# ComClone2.net
KiCad netlist of a schematic drawn in EAGLE
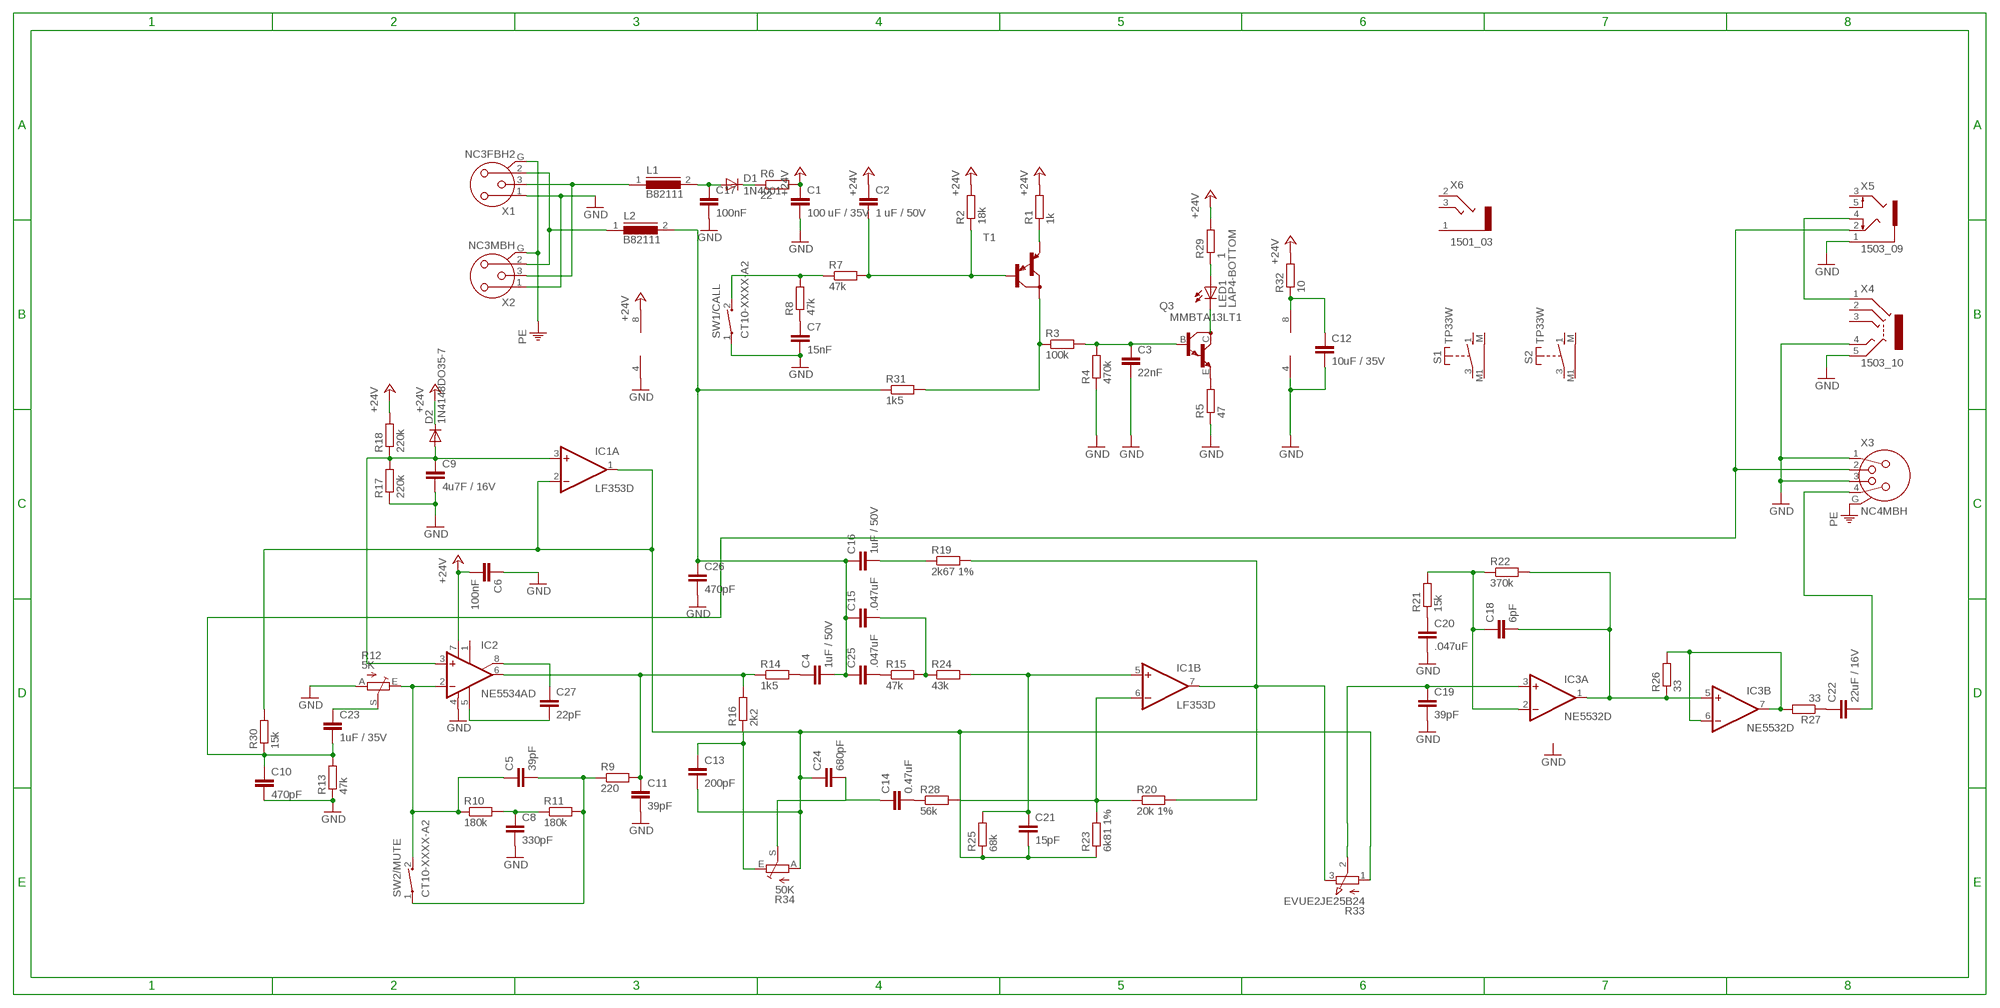
[diagram p0: schematic, sheet 1]

(export (version "E")
  (design (tool "Eeschema 10.0.6"))
  (components
    (comp (ref "C1")
      (value "100 uF / 35V")
      (footprint "eagle-import:C1206")
      (libsource (lib "eagle-import") (part "C-EUC1206"))
    )
    (comp (ref "C2")
      (value "1 uF / 50V")
      (footprint "eagle-import:C1206")
      (libsource (lib "eagle-import") (part "C-EUC1206"))
    )
    (comp (ref "C3")
      (value "22nF")
      (footprint "eagle-import:C0603")
      (libsource (lib "eagle-import") (part "C-EUC0603"))
    )
    (comp (ref "C4")
      (value "1uF / 50V")
      (footprint "eagle-import:C1206")
      (libsource (lib "eagle-import") (part "C-EUC1206"))
    )
    (comp (ref "C5")
      (value "39pF")
      (footprint "eagle-import:C0603")
      (libsource (lib "eagle-import") (part "C-EUC0603"))
    )
    (comp (ref "C6")
      (value "100nF")
      (footprint "eagle-import:C1206")
      (libsource (lib "eagle-import") (part "C-EUC1206"))
    )
    (comp (ref "C7")
      (value "15nF")
      (footprint "eagle-import:C0603")
      (libsource (lib "eagle-import") (part "C-EUC0603"))
    )
    (comp (ref "C8")
      (value "330pF")
      (footprint "eagle-import:C0603")
      (libsource (lib "eagle-import") (part "C-EUC0603"))
    )
    (comp (ref "C9")
      (value "4u7F / 16V")
      (footprint "eagle-import:C1206")
      (libsource (lib "eagle-import") (part "C-EUC1206"))
    )
    (comp (ref "C10")
      (value "470pF")
      (footprint "eagle-import:C0603")
      (libsource (lib "eagle-import") (part "C-EUC0603"))
    )
    (comp (ref "C11")
      (value "39pF")
      (footprint "eagle-import:C0603")
      (libsource (lib "eagle-import") (part "C-EUC0603"))
    )
    (comp (ref "C12")
      (value "10uF / 35V")
      (footprint "eagle-import:C1206")
      (libsource (lib "eagle-import") (part "C-EUC1206"))
    )
    (comp (ref "C13")
      (value "200pF")
      (footprint "eagle-import:C0603")
      (libsource (lib "eagle-import") (part "C-EUC0603"))
    )
    (comp (ref "C14")
      (value "0.47uF")
      (footprint "eagle-import:C0603")
      (libsource (lib "eagle-import") (part "C-EUC0603"))
    )
    (comp (ref "C15")
      (value ".047uF")
      (footprint "eagle-import:C1206")
      (libsource (lib "eagle-import") (part "C-EUC1206"))
    )
    (comp (ref "C16")
      (value "1uF / 50V")
      (footprint "eagle-import:C3225")
      (libsource (lib "eagle-import") (part "C-EUC3225"))
    )
    (comp (ref "C17")
      (value "100nF")
      (footprint "eagle-import:C1206")
      (libsource (lib "eagle-import") (part "C-EUC1206"))
    )
    (comp (ref "C18")
      (value "6pF")
      (footprint "eagle-import:C1206")
      (libsource (lib "eagle-import") (part "C-EUC1206"))
    )
    (comp (ref "C19")
      (value "39pF")
      (footprint "eagle-import:C1206")
      (libsource (lib "eagle-import") (part "C-EUC1206"))
    )
    (comp (ref "C20")
      (value ".047uF")
      (footprint "eagle-import:C1206")
      (libsource (lib "eagle-import") (part "C-EUC1206"))
    )
    (comp (ref "C21")
      (value "15pF")
      (footprint "eagle-import:C1206")
      (libsource (lib "eagle-import") (part "C-EUC1206"))
    )
    (comp (ref "C22")
      (value "22uF / 16V")
      (footprint "eagle-import:C1206")
      (libsource (lib "eagle-import") (part "C-EUC1206"))
    )
    (comp (ref "C23")
      (value "1uF / 35V")
      (footprint "eagle-import:C1206")
      (libsource (lib "eagle-import") (part "C-EUC1206"))
    )
    (comp (ref "C24")
      (value "680pF")
      (footprint "eagle-import:C0603")
      (libsource (lib "eagle-import") (part "C-EUC0603"))
    )
    (comp (ref "C25")
      (value ".047uF")
      (footprint "eagle-import:C0603")
      (libsource (lib "eagle-import") (part "C-EUC0603"))
    )
    (comp (ref "C26")
      (value "470pF")
      (footprint "eagle-import:C0603")
      (libsource (lib "eagle-import") (part "C-EUC0603"))
    )
    (comp (ref "C27")
      (value "22pF")
      (footprint "eagle-import:C0603")
      (libsource (lib "eagle-import") (part "C-EUC0603"))
    )
    (comp (ref "D1")
      (value "1N4001")
      (footprint "eagle-import:DO41-10")
      (libsource (lib "eagle-import") (part "1N4004"))
    )
    (comp (ref "D2")
      (value "1N4148DO35-7")
      (footprint "eagle-import:DO35-7")
      (libsource (lib "eagle-import") (part "1N4148DO35-7"))
    )
    (comp (ref "IC1")
      (value "LF353D")
      (footprint "eagle-import:SO08")
      (libsource (lib "eagle-import") (part "LF353D"))
    )
    (comp (ref "IC2")
      (value "NE5534AD")
      (footprint "eagle-import:SO08")
      (libsource (lib "eagle-import") (part "NE5534DA"))
    )
    (comp (ref "IC3")
      (value "NE5532D")
      (footprint "eagle-import:SO08")
      (libsource (lib "eagle-import") (part "NE5532D"))
    )
    (comp (ref "L1")
      (value "B82111")
      (footprint "eagle-import:SUKW1-30")
      (libsource (lib "eagle-import") (part "B82111"))
    )
    (comp (ref "L2")
      (value "B82111")
      (footprint "eagle-import:SUKW1-30")
      (libsource (lib "eagle-import") (part "B82111"))
    )
    (comp (ref "LED1")
      (value "LAP4-BOTTOM")
      (footprint "eagle-import:P47F-BOTTOM")
      (libsource (lib "eagle-import") (part "P4-BOTTOMLA"))
    )
    (comp (ref "Q3")
      (value "MMBTA13LT1")
      (footprint "eagle-import:SOT23-BEC")
      (libsource (lib "eagle-import") (part "MMBTA13LT1"))
    )
    (comp (ref "R1")
      (value "1k")
      (footprint "eagle-import:R0603")
      (libsource (lib "eagle-import") (part "R-EU_R0603"))
    )
    (comp (ref "R2")
      (value "18k")
      (footprint "eagle-import:R0603")
      (libsource (lib "eagle-import") (part "R-EU_R0603"))
    )
    (comp (ref "R3")
      (value "100k")
      (footprint "eagle-import:R0603")
      (libsource (lib "eagle-import") (part "R-EU_R0603"))
    )
    (comp (ref "R4")
      (value "470k")
      (footprint "eagle-import:R0603")
      (libsource (lib "eagle-import") (part "R-EU_R0603"))
    )
    (comp (ref "R5")
      (value "47")
      (footprint "eagle-import:M1206")
      (libsource (lib "eagle-import") (part "R-EU_M1206"))
    )
    (comp (ref "R6")
      (value "22")
      (footprint "eagle-import:M1206")
      (libsource (lib "eagle-import") (part "R-EU_M1206"))
    )
    (comp (ref "R7")
      (value "47k")
      (footprint "eagle-import:R0603")
      (libsource (lib "eagle-import") (part "R-EU_R0603"))
    )
    (comp (ref "R8")
      (value "47k")
      (footprint "eagle-import:R0603")
      (libsource (lib "eagle-import") (part "R-EU_R0603"))
    )
    (comp (ref "R9")
      (value "220")
      (footprint "eagle-import:R0603")
      (libsource (lib "eagle-import") (part "R-EU_R0603"))
    )
    (comp (ref "R10")
      (value "180k")
      (footprint "eagle-import:R0603")
      (libsource (lib "eagle-import") (part "R-EU_R0603"))
    )
    (comp (ref "R11")
      (value "180k")
      (footprint "eagle-import:R0603")
      (libsource (lib "eagle-import") (part "R-EU_R0603"))
    )
    (comp (ref "R12")
      (value "5K")
      (footprint "eagle-import:PT-10S")
      (libsource (lib "eagle-import") (part "TRIM_EU-PT10S"))
    )
    (comp (ref "R13")
      (value "47k")
      (footprint "eagle-import:R0603")
      (libsource (lib "eagle-import") (part "R-EU_R0603"))
    )
    (comp (ref "R14")
      (value "1k5")
      (footprint "eagle-import:R0603")
      (libsource (lib "eagle-import") (part "R-EU_R0603"))
    )
    (comp (ref "R15")
      (value "47k")
      (footprint "eagle-import:R0603")
      (libsource (lib "eagle-import") (part "R-EU_R0603"))
    )
    (comp (ref "R16")
      (value "2k2")
      (footprint "eagle-import:R0603")
      (libsource (lib "eagle-import") (part "R-EU_R0603"))
    )
    (comp (ref "R17")
      (value "220k")
      (footprint "eagle-import:M1206")
      (libsource (lib "eagle-import") (part "R-EU_M1206"))
    )
    (comp (ref "R18")
      (value "220k")
      (footprint "eagle-import:M1206")
      (libsource (lib "eagle-import") (part "R-EU_M1206"))
    )
    (comp (ref "R19")
      (value "2k67 1%")
      (footprint "eagle-import:M1206")
      (libsource (lib "eagle-import") (part "R-EU_M1206"))
    )
    (comp (ref "R20")
      (value "20k 1%")
      (footprint "eagle-import:R0603")
      (libsource (lib "eagle-import") (part "R-EU_R0603"))
    )
    (comp (ref "R21")
      (value "15k")
      (footprint "eagle-import:M1206")
      (libsource (lib "eagle-import") (part "R-EU_M1206"))
    )
    (comp (ref "R22")
      (value "370k")
      (footprint "eagle-import:R0603")
      (libsource (lib "eagle-import") (part "R-EU_R0603"))
    )
    (comp (ref "R23")
      (value "6k81 1%")
      (footprint "eagle-import:R0603")
      (libsource (lib "eagle-import") (part "R-EU_R0603"))
    )
    (comp (ref "R24")
      (value "43k")
      (footprint "eagle-import:R0603")
      (libsource (lib "eagle-import") (part "R-EU_R0603"))
    )
    (comp (ref "R25")
      (value "68k")
      (footprint "eagle-import:R0603")
      (libsource (lib "eagle-import") (part "R-EU_R0603"))
    )
    (comp (ref "R26")
      (value "33")
      (footprint "eagle-import:M1206")
      (libsource (lib "eagle-import") (part "R-EU_M1206"))
    )
    (comp (ref "R27")
      (value "33")
      (footprint "eagle-import:M1206")
      (libsource (lib "eagle-import") (part "R-EU_M1206"))
    )
    (comp (ref "R28")
      (value "56k")
      (footprint "eagle-import:R0603")
      (libsource (lib "eagle-import") (part "R-EU_R0603"))
    )
    (comp (ref "R29")
      (value "1")
      (footprint "eagle-import:M1206")
      (libsource (lib "eagle-import") (part "R-EU_M1206"))
    )
    (comp (ref "R30")
      (value "15k")
      (footprint "eagle-import:R0603")
      (libsource (lib "eagle-import") (part "R-EU_R0603"))
    )
    (comp (ref "R31")
      (value "1k5")
      (footprint "eagle-import:R0603")
      (libsource (lib "eagle-import") (part "R-EU_R0603"))
    )
    (comp (ref "R32")
      (value "10")
      (footprint "eagle-import:M1206")
      (libsource (lib "eagle-import") (part "R-EU_M1206"))
    )
    (comp (ref "R33")
      (value "EVUE2JE25B24")
      (footprint "eagle-import:EVUEXXJ")
      (libsource (lib "eagle-import") (part "EVUJE2"))
    )
    (comp (ref "R34")
      (value "50K")
      (footprint "eagle-import:PT-10S")
      (libsource (lib "eagle-import") (part "TRIM_EU-PT10S"))
    )
    (comp (ref "S1")
      (value "TP33W")
      (footprint "eagle-import:TP33W")
      (libsource (lib "eagle-import") (part "TP33W"))
    )
    (comp (ref "S2")
      (value "TP33W")
      (footprint "eagle-import:TP33W")
      (libsource (lib "eagle-import") (part "TP33W"))
    )
    (comp (ref "SW1/CALL")
      (value "CT10-XXXX-A2")
      (footprint "eagle-import:CT10-XXXX-A2")
      (libsource (lib "eagle-import") (part "CT10-XXXX-A2"))
    )
    (comp (ref "SW2/MUTE")
      (value "CT10-XXXX-A2")
      (footprint "eagle-import:CT10-XXXX-A2")
      (libsource (lib "eagle-import") (part "CT10-XXXX-A2"))
    )
    (comp (ref "T1")
      (value "MMBTA64LT1-PNP_DARL-SOT23-BEC")
      (footprint "eagle-import:SOT23-BEC")
      (libsource (lib "eagle-import") (part "-PNP_DARL-SOT23-BECMMBTA64LT1"))
    )
    (comp (ref "X1")
      (value "NC3FBH2")
      (footprint "eagle-import:NC3FBH2")
      (libsource (lib "eagle-import") (part "NC3FBH2"))
    )
    (comp (ref "X2")
      (value "NC3MBH")
      (footprint "eagle-import:NC3MBH")
      (fields (field (name "MF") "NEUTRIK"))
      (libsource (lib "eagle-import") (part "NC3MBH"))
    )
    (comp (ref "X3")
      (value "NC4MBH")
      (footprint "eagle-import:NC4MBH")
      (libsource (lib "eagle-import") (part "NC4MBH"))
    )
    (comp (ref "X4")
      (value "1503_10")
      (footprint "eagle-import:1503_10")
      (libsource (lib "eagle-import") (part "1503_10"))
    )
    (comp (ref "X5")
      (value "1503_09")
      (footprint "eagle-import:1503_09")
      (libsource (lib "eagle-import") (part "1503_09"))
    )
    (comp (ref "X6")
      (value "1501_03")
      (footprint "eagle-import:1501_03")
      (libsource (lib "eagle-import") (part "1501_03"))
    )
  )
  (nets
    (net (code "1") (name "+24V") (class "Default")
      (node (ref "C1") (pin "1") (pinfunction "1_1") (pintype "passive"))
      (node (ref "C2") (pin "1") (pinfunction "1_1") (pintype "passive"))
      (node (ref "C6") (pin "2") (pinfunction "2_2") (pintype "passive"))
      (node (ref "D2") (pin "C") (pinfunction "C_C") (pintype "passive"))
      (node (ref "IC1") (pin "8") (pinfunction "V+_8") (pintype "power_in"))
      (node (ref "IC2") (pin "7") (pinfunction "V+_7") (pintype "power_in"))
      (node (ref "R1") (pin "2") (pinfunction "2_2") (pintype "passive"))
      (node (ref "R18") (pin "2") (pinfunction "2_2") (pintype "passive"))
      (node (ref "R2") (pin "2") (pinfunction "2_2") (pintype "passive"))
      (node (ref "R29") (pin "2") (pinfunction "2_2") (pintype "passive"))
      (node (ref "R32") (pin "2") (pinfunction "2_2") (pintype "passive"))
      (node (ref "R6") (pin "2") (pinfunction "2_2") (pintype "passive"))
    )
    (net (code "2") (name "GND") (class "Default")
      (node (ref "C1") (pin "2") (pinfunction "2_2") (pintype "passive"))
      (node (ref "C10") (pin "2") (pinfunction "2_2") (pintype "passive"))
      (node (ref "C11") (pin "2") (pinfunction "2_2") (pintype "passive"))
      (node (ref "C12") (pin "2") (pinfunction "2_2") (pintype "passive"))
      (node (ref "C17") (pin "2") (pinfunction "2_2") (pintype "passive"))
      (node (ref "C19") (pin "2") (pinfunction "2_2") (pintype "passive"))
      (node (ref "C20") (pin "2") (pinfunction "2_2") (pintype "passive"))
      (node (ref "C26") (pin "2") (pinfunction "2_2") (pintype "passive"))
      (node (ref "C3") (pin "2") (pinfunction "2_2") (pintype "passive"))
      (node (ref "C6") (pin "1") (pinfunction "1_1") (pintype "passive"))
      (node (ref "C7") (pin "2") (pinfunction "2_2") (pintype "passive"))
      (node (ref "C8") (pin "2") (pinfunction "2_2") (pintype "passive"))
      (node (ref "C9") (pin "2") (pinfunction "2_2") (pintype "passive"))
      (node (ref "IC1") (pin "4") (pinfunction "V-_4") (pintype "power_in"))
      (node (ref "IC2") (pin "4") (pinfunction "V-_4") (pintype "power_in"))
      (node (ref "IC3") (pin "4") (pinfunction "V-_4") (pintype "power_in"))
      (node (ref "R12") (pin "A") (pinfunction "A_A") (pintype "passive"))
      (node (ref "R13") (pin "1") (pinfunction "1_1") (pintype "passive"))
      (node (ref "R17") (pin "1") (pinfunction "1_1") (pintype "passive"))
      (node (ref "R4") (pin "1") (pinfunction "1_1") (pintype "passive"))
      (node (ref "R5") (pin "1") (pinfunction "1_1") (pintype "passive"))
      (node (ref "SW1/CALL") (pin "1") (pinfunction "1_1") (pintype "passive"))
      (node (ref "X1") (pin "1") (pinfunction "1_1") (pintype "passive"))
      (node (ref "X2") (pin "1") (pinfunction "1_1") (pintype "passive"))
      (node (ref "X3") (pin "1") (pinfunction "1_1") (pintype "passive"))
      (node (ref "X3") (pin "3") (pinfunction "3_3") (pintype "passive"))
      (node (ref "X4") (pin "4") (pinfunction "4_4") (pintype "passive"))
      (node (ref "X4") (pin "5") (pinfunction "5_5") (pintype "passive"))
      (node (ref "X5") (pin "1") (pinfunction "1_1") (pintype "passive"))
    )
    (net (code "3") (name "Net-(C2-Pad2)") (class "Default")
      (node (ref "C2") (pin "2") (pinfunction "2_2") (pintype "passive"))
      (node (ref "R2") (pin "1") (pinfunction "1_1") (pintype "passive"))
      (node (ref "R7") (pin "2") (pinfunction "2_2") (pintype "passive"))
      (node (ref "T1") (pin "B") (pinfunction "B_B") (pintype "passive"))
    )
    (net (code "4") (name "Net-(C3-Pad1)") (class "Default")
      (node (ref "C3") (pin "1") (pinfunction "1_1") (pintype "passive"))
      (node (ref "Q3") (pin "B") (pinfunction "B_B") (pintype "passive"))
      (node (ref "R3") (pin "2") (pinfunction "2_2") (pintype "passive"))
      (node (ref "R4") (pin "2") (pinfunction "2_2") (pintype "passive"))
    )
    (net (code "5") (name "Net-(C4-Pad1)") (class "Default")
      (node (ref "C4") (pin "1") (pinfunction "1_1") (pintype "passive"))
      (node (ref "R14") (pin "2") (pinfunction "2_2") (pintype "passive"))
    )
    (net (code "6") (name "Net-(C5-Pad2)") (class "Default")
      (node (ref "C5") (pin "2") (pinfunction "2_2") (pintype "passive"))
      (node (ref "R11") (pin "2") (pinfunction "2_2") (pintype "passive"))
      (node (ref "R9") (pin "1") (pinfunction "1_1") (pintype "passive"))
      (node (ref "SW2/MUTE") (pin "1") (pinfunction "1_1") (pintype "passive"))
    )
    (net (code "7") (name "Net-(C7-Pad1)") (class "Default")
      (node (ref "C7") (pin "1") (pinfunction "1_1") (pintype "passive"))
      (node (ref "R8") (pin "1") (pinfunction "1_1") (pintype "passive"))
    )
    (net (code "8") (name "Net-(C8-Pad1)") (class "Default")
      (node (ref "C8") (pin "1") (pinfunction "1_1") (pintype "passive"))
      (node (ref "R10") (pin "2") (pinfunction "2_2") (pintype "passive"))
      (node (ref "R11") (pin "1") (pinfunction "1_1") (pintype "passive"))
    )
    (net (code "9") (name "Net-(C10-Pad1)") (class "Default")
      (node (ref "C10") (pin "1") (pinfunction "1_1") (pintype "passive"))
      (node (ref "C23") (pin "2") (pinfunction "2_2") (pintype "passive"))
      (node (ref "R13") (pin "2") (pinfunction "2_2") (pintype "passive"))
      (node (ref "R30") (pin "1") (pinfunction "1_1") (pintype "passive"))
      (node (ref "X3") (pin "2") (pinfunction "2_2") (pintype "passive"))
      (node (ref "X5") (pin "2") (pinfunction "2_2") (pintype "passive"))
    )
    (net (code "10") (name "Net-(C13-Pad1)") (class "Default")
      (node (ref "C13") (pin "1") (pinfunction "1_1") (pintype "passive"))
      (node (ref "R16") (pin "1") (pinfunction "1_1") (pintype "passive"))
      (node (ref "R34") (pin "E") (pinfunction "E_E") (pintype "passive"))
    )
    (net (code "11") (name "Net-(C14-Pad1)") (class "Default")
      (node (ref "C14") (pin "1") (pinfunction "1_1") (pintype "passive"))
      (node (ref "C24") (pin "2") (pinfunction "2_2") (pintype "passive"))
      (node (ref "R34") (pin "S") (pinfunction "S_S") (pintype "passive"))
    )
    (net (code "12") (name "Net-(C14-Pad2)") (class "Default")
      (node (ref "C14") (pin "2") (pinfunction "2_2") (pintype "passive"))
      (node (ref "R28") (pin "1") (pinfunction "1_1") (pintype "passive"))
    )
    (net (code "13") (name "Net-(C15-Pad1)") (class "Default")
      (node (ref "C15") (pin "1") (pinfunction "1_1") (pintype "passive"))
      (node (ref "C16") (pin "1") (pinfunction "1_1") (pintype "passive"))
      (node (ref "C25") (pin "1") (pinfunction "1_1") (pintype "passive"))
      (node (ref "C26") (pin "1") (pinfunction "1_1") (pintype "passive"))
      (node (ref "C4") (pin "2") (pinfunction "2_2") (pintype "passive"))
      (node (ref "L2") (pin "2") (pinfunction "2_2") (pintype "passive"))
      (node (ref "R31") (pin "1") (pinfunction "1_1") (pintype "passive"))
    )
    (net (code "14") (name "Net-(C15-Pad2)") (class "Default")
      (node (ref "C15") (pin "2") (pinfunction "2_2") (pintype "passive"))
      (node (ref "R15") (pin "2") (pinfunction "2_2") (pintype "passive"))
      (node (ref "R24") (pin "1") (pinfunction "1_1") (pintype "passive"))
    )
    (net (code "15") (name "Net-(C16-Pad2)") (class "Default")
      (node (ref "C16") (pin "2") (pinfunction "2_2") (pintype "passive"))
      (node (ref "R19") (pin "1") (pinfunction "1_1") (pintype "passive"))
    )
    (net (code "16") (name "Net-(C17-Pad1)") (class "Default")
      (node (ref "C17") (pin "1") (pinfunction "1_1") (pintype "passive"))
      (node (ref "D1") (pin "A") (pinfunction "A_A") (pintype "passive"))
      (node (ref "L1") (pin "2") (pinfunction "2_2") (pintype "passive"))
    )
    (net (code "17") (name "Net-(C20-Pad1)") (class "Default")
      (node (ref "C20") (pin "1") (pinfunction "1_1") (pintype "passive"))
      (node (ref "R21") (pin "1") (pinfunction "1_1") (pintype "passive"))
    )
    (net (code "18") (name "Net-(C22-Pad1)") (class "Default")
      (node (ref "C22") (pin "1") (pinfunction "1_1") (pintype "passive"))
      (node (ref "R27") (pin "1") (pinfunction "1_1") (pintype "passive"))
    )
    (net (code "19") (name "Net-(C22-Pad2)") (class "Default")
      (node (ref "C22") (pin "2") (pinfunction "2_2") (pintype "passive"))
      (node (ref "X3") (pin "4") (pinfunction "4_4") (pintype "passive"))
    )
    (net (code "20") (name "Net-(C23-Pad1)") (class "Default")
      (node (ref "C23") (pin "1") (pinfunction "1_1") (pintype "passive"))
      (node (ref "R12") (pin "S") (pinfunction "S_S") (pintype "passive"))
    )
    (net (code "21") (name "Net-(C25-Pad2)") (class "Default")
      (node (ref "C25") (pin "2") (pinfunction "2_2") (pintype "passive"))
      (node (ref "R15") (pin "1") (pinfunction "1_1") (pintype "passive"))
    )
    (net (code "22") (name "Net-(D1-PadC)") (class "Default")
      (node (ref "D1") (pin "C") (pinfunction "C_C") (pintype "passive"))
      (node (ref "R6") (pin "1") (pinfunction "1_1") (pintype "passive"))
    )
    (net (code "23") (name "Net-(IC1A-+IN)") (class "Default")
      (node (ref "C9") (pin "1") (pinfunction "1_1") (pintype "passive"))
      (node (ref "D2") (pin "A") (pinfunction "A_A") (pintype "passive"))
      (node (ref "IC1") (pin "3") (pinfunction "+IN_3") (pintype "input"))
      (node (ref "IC2") (pin "3") (pinfunction "+IN_3") (pintype "input"))
      (node (ref "R17") (pin "2") (pinfunction "2_2") (pintype "passive"))
      (node (ref "R18") (pin "1") (pinfunction "1_1") (pintype "passive"))
    )
    (net (code "24") (name "Net-(IC1A--IN)") (class "Default")
      (node (ref "C13") (pin "2") (pinfunction "2_2") (pintype "passive"))
      (node (ref "C21") (pin "2") (pinfunction "2_2") (pintype "passive"))
      (node (ref "C24") (pin "1") (pinfunction "1_1") (pintype "passive"))
      (node (ref "IC1") (pin "1") (pinfunction "OUT_1") (pintype "output"))
      (node (ref "IC1") (pin "2") (pinfunction "-IN_2") (pintype "input"))
      (node (ref "R23") (pin "1") (pinfunction "1_1") (pintype "passive"))
      (node (ref "R25") (pin "1") (pinfunction "1_1") (pintype "passive"))
      (node (ref "R30") (pin "2") (pinfunction "2_2") (pintype "passive"))
      (node (ref "R33") (pin "1") (pinfunction "A_1") (pintype "passive"))
      (node (ref "R34") (pin "A") (pinfunction "A_A") (pintype "passive"))
    )
    (net (code "25") (name "Net-(IC1B-+IN)") (class "Default")
      (node (ref "C21") (pin "1") (pinfunction "1_1") (pintype "passive"))
      (node (ref "IC1") (pin "5") (pinfunction "+IN_5") (pintype "input"))
      (node (ref "R24") (pin "2") (pinfunction "2_2") (pintype "passive"))
      (node (ref "R25") (pin "2") (pinfunction "2_2") (pintype "passive"))
    )
    (net (code "26") (name "Net-(IC1B--IN)") (class "Default")
      (node (ref "IC1") (pin "6") (pinfunction "-IN_6") (pintype "input"))
      (node (ref "R20") (pin "1") (pinfunction "1_1") (pintype "passive"))
      (node (ref "R23") (pin "2") (pinfunction "2_2") (pintype "passive"))
      (node (ref "R28") (pin "2") (pinfunction "2_2") (pintype "passive"))
    )
    (net (code "27") (name "Net-(IC1B-OUT)") (class "Default")
      (node (ref "IC1") (pin "7") (pinfunction "OUT_7") (pintype "output"))
      (node (ref "R19") (pin "2") (pinfunction "2_2") (pintype "passive"))
      (node (ref "R20") (pin "2") (pinfunction "2_2") (pintype "passive"))
      (node (ref "R33") (pin "3") (pinfunction "E_3") (pintype "passive"))
    )
    (net (code "28") (name "Net-(IC2--IN)") (class "Default")
      (node (ref "C5") (pin "1") (pinfunction "1_1") (pintype "passive"))
      (node (ref "IC2") (pin "2") (pinfunction "-IN_2") (pintype "input"))
      (node (ref "R10") (pin "1") (pinfunction "1_1") (pintype "passive"))
      (node (ref "R12") (pin "E") (pinfunction "E_E") (pintype "passive"))
      (node (ref "SW2/MUTE") (pin "2") (pinfunction "2_2") (pintype "passive"))
    )
    (net (code "29") (name "Net-(IC2-CMP)") (class "Default")
      (node (ref "C27") (pin "2") (pinfunction "2_2") (pintype "passive"))
      (node (ref "IC2") (pin "5") (pinfunction "CMP_5") (pintype "passive"))
    )
    (net (code "30") (name "Net-(IC2-ON{slash}CMP)") (class "Default")
      (node (ref "C27") (pin "1") (pinfunction "1_1") (pintype "passive"))
      (node (ref "IC2") (pin "8") (pinfunction "ON/CMP_8") (pintype "passive"))
    )
    (net (code "31") (name "Net-(IC2-OUT)") (class "Default")
      (node (ref "C11") (pin "1") (pinfunction "1_1") (pintype "passive"))
      (node (ref "IC2") (pin "6") (pinfunction "OUT_6") (pintype "output"))
      (node (ref "R14") (pin "1") (pinfunction "1_1") (pintype "passive"))
      (node (ref "R16") (pin "2") (pinfunction "2_2") (pintype "passive"))
      (node (ref "R9") (pin "2") (pinfunction "2_2") (pintype "passive"))
    )
    (net (code "32") (name "Net-(IC3A-+IN)") (class "Default")
      (node (ref "C19") (pin "1") (pinfunction "1_1") (pintype "passive"))
      (node (ref "IC3") (pin "3") (pinfunction "+IN_3") (pintype "input"))
      (node (ref "R33") (pin "2") (pinfunction "S_2") (pintype "passive"))
    )
    (net (code "33") (name "Net-(IC3A--IN)") (class "Default")
      (node (ref "C18") (pin "1") (pinfunction "1_1") (pintype "passive"))
      (node (ref "IC3") (pin "2") (pinfunction "-IN_2") (pintype "input"))
      (node (ref "R21") (pin "2") (pinfunction "2_2") (pintype "passive"))
      (node (ref "R22") (pin "1") (pinfunction "1_1") (pintype "passive"))
    )
    (net (code "34") (name "Net-(IC3A-OUT)") (class "Default")
      (node (ref "C18") (pin "2") (pinfunction "2_2") (pintype "passive"))
      (node (ref "IC3") (pin "1") (pinfunction "OUT_1") (pintype "output"))
      (node (ref "IC3") (pin "5") (pinfunction "+IN_5") (pintype "input"))
      (node (ref "R22") (pin "2") (pinfunction "2_2") (pintype "passive"))
      (node (ref "R26") (pin "1") (pinfunction "1_1") (pintype "passive"))
    )
    (net (code "35") (name "Net-(IC3B--IN)") (class "Default")
      (node (ref "IC3") (pin "6") (pinfunction "-IN_6") (pintype "input"))
      (node (ref "IC3") (pin "7") (pinfunction "OUT_7") (pintype "output"))
      (node (ref "R26") (pin "2") (pinfunction "2_2") (pintype "passive"))
      (node (ref "R27") (pin "2") (pinfunction "2_2") (pintype "passive"))
    )
    (net (code "36") (name "Net-(IC3C-V+)") (class "Default")
      (node (ref "C12") (pin "1") (pinfunction "1_1") (pintype "passive"))
      (node (ref "IC3") (pin "8") (pinfunction "V+_8") (pintype "power_in"))
      (node (ref "R32") (pin "1") (pinfunction "1_1") (pintype "passive"))
    )
    (net (code "37") (name "Net-(L1-Pad1)") (class "Default")
      (node (ref "L1") (pin "1") (pinfunction "1_1") (pintype "passive"))
      (node (ref "X1") (pin "3") (pinfunction "3_3") (pintype "passive"))
      (node (ref "X2") (pin "3") (pinfunction "3_3") (pintype "passive"))
    )
    (net (code "38") (name "Net-(L2-Pad1)") (class "Default")
      (node (ref "L2") (pin "1") (pinfunction "1_1") (pintype "passive"))
      (node (ref "X1") (pin "2") (pinfunction "2_2") (pintype "passive"))
      (node (ref "X2") (pin "2") (pinfunction "2_2") (pintype "passive"))
    )
    (net (code "39") (name "Net-(LED1-PadA)") (class "Default")
      (node (ref "LED1") (pin "A") (pinfunction "A_A") (pintype "passive"))
      (node (ref "R29") (pin "1") (pinfunction "1_1") (pintype "passive"))
    )
    (net (code "40") (name "Net-(LED1-PadC)") (class "Default")
      (node (ref "LED1") (pin "C") (pinfunction "C_C") (pintype "passive"))
      (node (ref "Q3") (pin "C") (pinfunction "C_C") (pintype "passive"))
    )
    (net (code "41") (name "Net-(Q3-PadE)") (class "Default")
      (node (ref "Q3") (pin "E") (pinfunction "E_E") (pintype "passive"))
      (node (ref "R5") (pin "2") (pinfunction "2_2") (pintype "passive"))
    )
    (net (code "42") (name "Net-(R1-Pad1)") (class "Default")
      (node (ref "R1") (pin "1") (pinfunction "1_1") (pintype "passive"))
      (node (ref "T1") (pin "E") (pinfunction "E_E") (pintype "passive"))
    )
    (net (code "43") (name "Net-(R3-Pad1)") (class "Default")
      (node (ref "R3") (pin "1") (pinfunction "1_1") (pintype "passive"))
      (node (ref "R31") (pin "2") (pinfunction "2_2") (pintype "passive"))
      (node (ref "T1") (pin "C") (pinfunction "C_C") (pintype "passive"))
    )
    (net (code "44") (name "Net-(R7-Pad1)") (class "Default")
      (node (ref "R7") (pin "1") (pinfunction "1_1") (pintype "passive"))
      (node (ref "R8") (pin "2") (pinfunction "2_2") (pintype "passive"))
      (node (ref "SW1/CALL") (pin "2") (pinfunction "2_2") (pintype "passive"))
    )
    (net (code "45") (name "Net-(X4-Pad1)") (class "Default")
      (node (ref "X4") (pin "1") (pinfunction "1_1") (pintype "passive"))
      (node (ref "X5") (pin "4") (pinfunction "4_4") (pintype "passive"))
    )
    (net (code "46") (name "PE") (class "Default")
      (node (ref "X1") (pin "G") (pinfunction "G_G") (pintype "passive"))
      (node (ref "X2") (pin "G") (pinfunction "G_G") (pintype "passive"))
      (node (ref "X3") (pin "G") (pinfunction "G_G") (pintype "passive"))
    )
    (net (code "47") (name "unconnected-(IC2-ON-Pad1)") (class "Default")
      (node (ref "IC2") (pin "1") (pinfunction "ON_1") (pintype "passive"))
    )
    (net (code "48") (name "unconnected-(S1-M-PadM1)") (class "Default")
      (node (ref "S1") (pin "M1") (pinfunction "M_M1") (pintype "passive"))
    )
    (net (code "49") (name "unconnected-(S1-P-Pad3)") (class "Default")
      (node (ref "S1") (pin "3") (pinfunction "P_3") (pintype "passive"))
    )
    (net (code "50") (name "unconnected-(S1-PadM)") (class "Default")
      (node (ref "S1") (pin "M") (pinfunction "M_M") (pintype "passive"))
    )
    (net (code "51") (name "unconnected-(S1-S-Pad1)") (class "Default")
      (node (ref "S1") (pin "1") (pinfunction "S_1") (pintype "passive"))
    )
    (net (code "52") (name "unconnected-(S2-M-PadM1)") (class "Default")
      (node (ref "S2") (pin "M1") (pinfunction "M_M1") (pintype "passive"))
    )
    (net (code "53") (name "unconnected-(S2-P-Pad3)") (class "Default")
      (node (ref "S2") (pin "3") (pinfunction "P_3") (pintype "passive"))
    )
    (net (code "54") (name "unconnected-(S2-PadM)") (class "Default")
      (node (ref "S2") (pin "M") (pinfunction "M_M") (pintype "passive"))
    )
    (net (code "55") (name "unconnected-(S2-S-Pad1)") (class "Default")
      (node (ref "S2") (pin "1") (pinfunction "S_1") (pintype "passive"))
    )
    (net (code "56") (name "unconnected-(X4-Pad2)") (class "Default")
      (node (ref "X4") (pin "2") (pinfunction "2_2") (pintype "passive"))
    )
    (net (code "57") (name "unconnected-(X4-Pad3)") (class "Default")
      (node (ref "X4") (pin "3") (pinfunction "3_3") (pintype "passive"))
    )
    (net (code "58") (name "unconnected-(X5-Pad3)") (class "Default")
      (node (ref "X5") (pin "3") (pinfunction "3_3") (pintype "passive"))
    )
    (net (code "59") (name "unconnected-(X5-Pad5)") (class "Default")
      (node (ref "X5") (pin "5") (pinfunction "5_5") (pintype "passive"))
    )
    (net (code "60") (name "unconnected-(X6-Pad1)") (class "Default")
      (node (ref "X6") (pin "1") (pinfunction "1_1") (pintype "passive"))
    )
    (net (code "61") (name "unconnected-(X6-Pad2)") (class "Default")
      (node (ref "X6") (pin "2") (pinfunction "2_2") (pintype "passive"))
    )
    (net (code "62") (name "unconnected-(X6-Pad3)") (class "Default")
      (node (ref "X6") (pin "3") (pinfunction "3_3") (pintype "passive"))
    )
  )
)
